# BusPirate-v3_6a-LTS-placed4-plane2-final.net
KiCad netlist of a schematic drawn in EAGLE
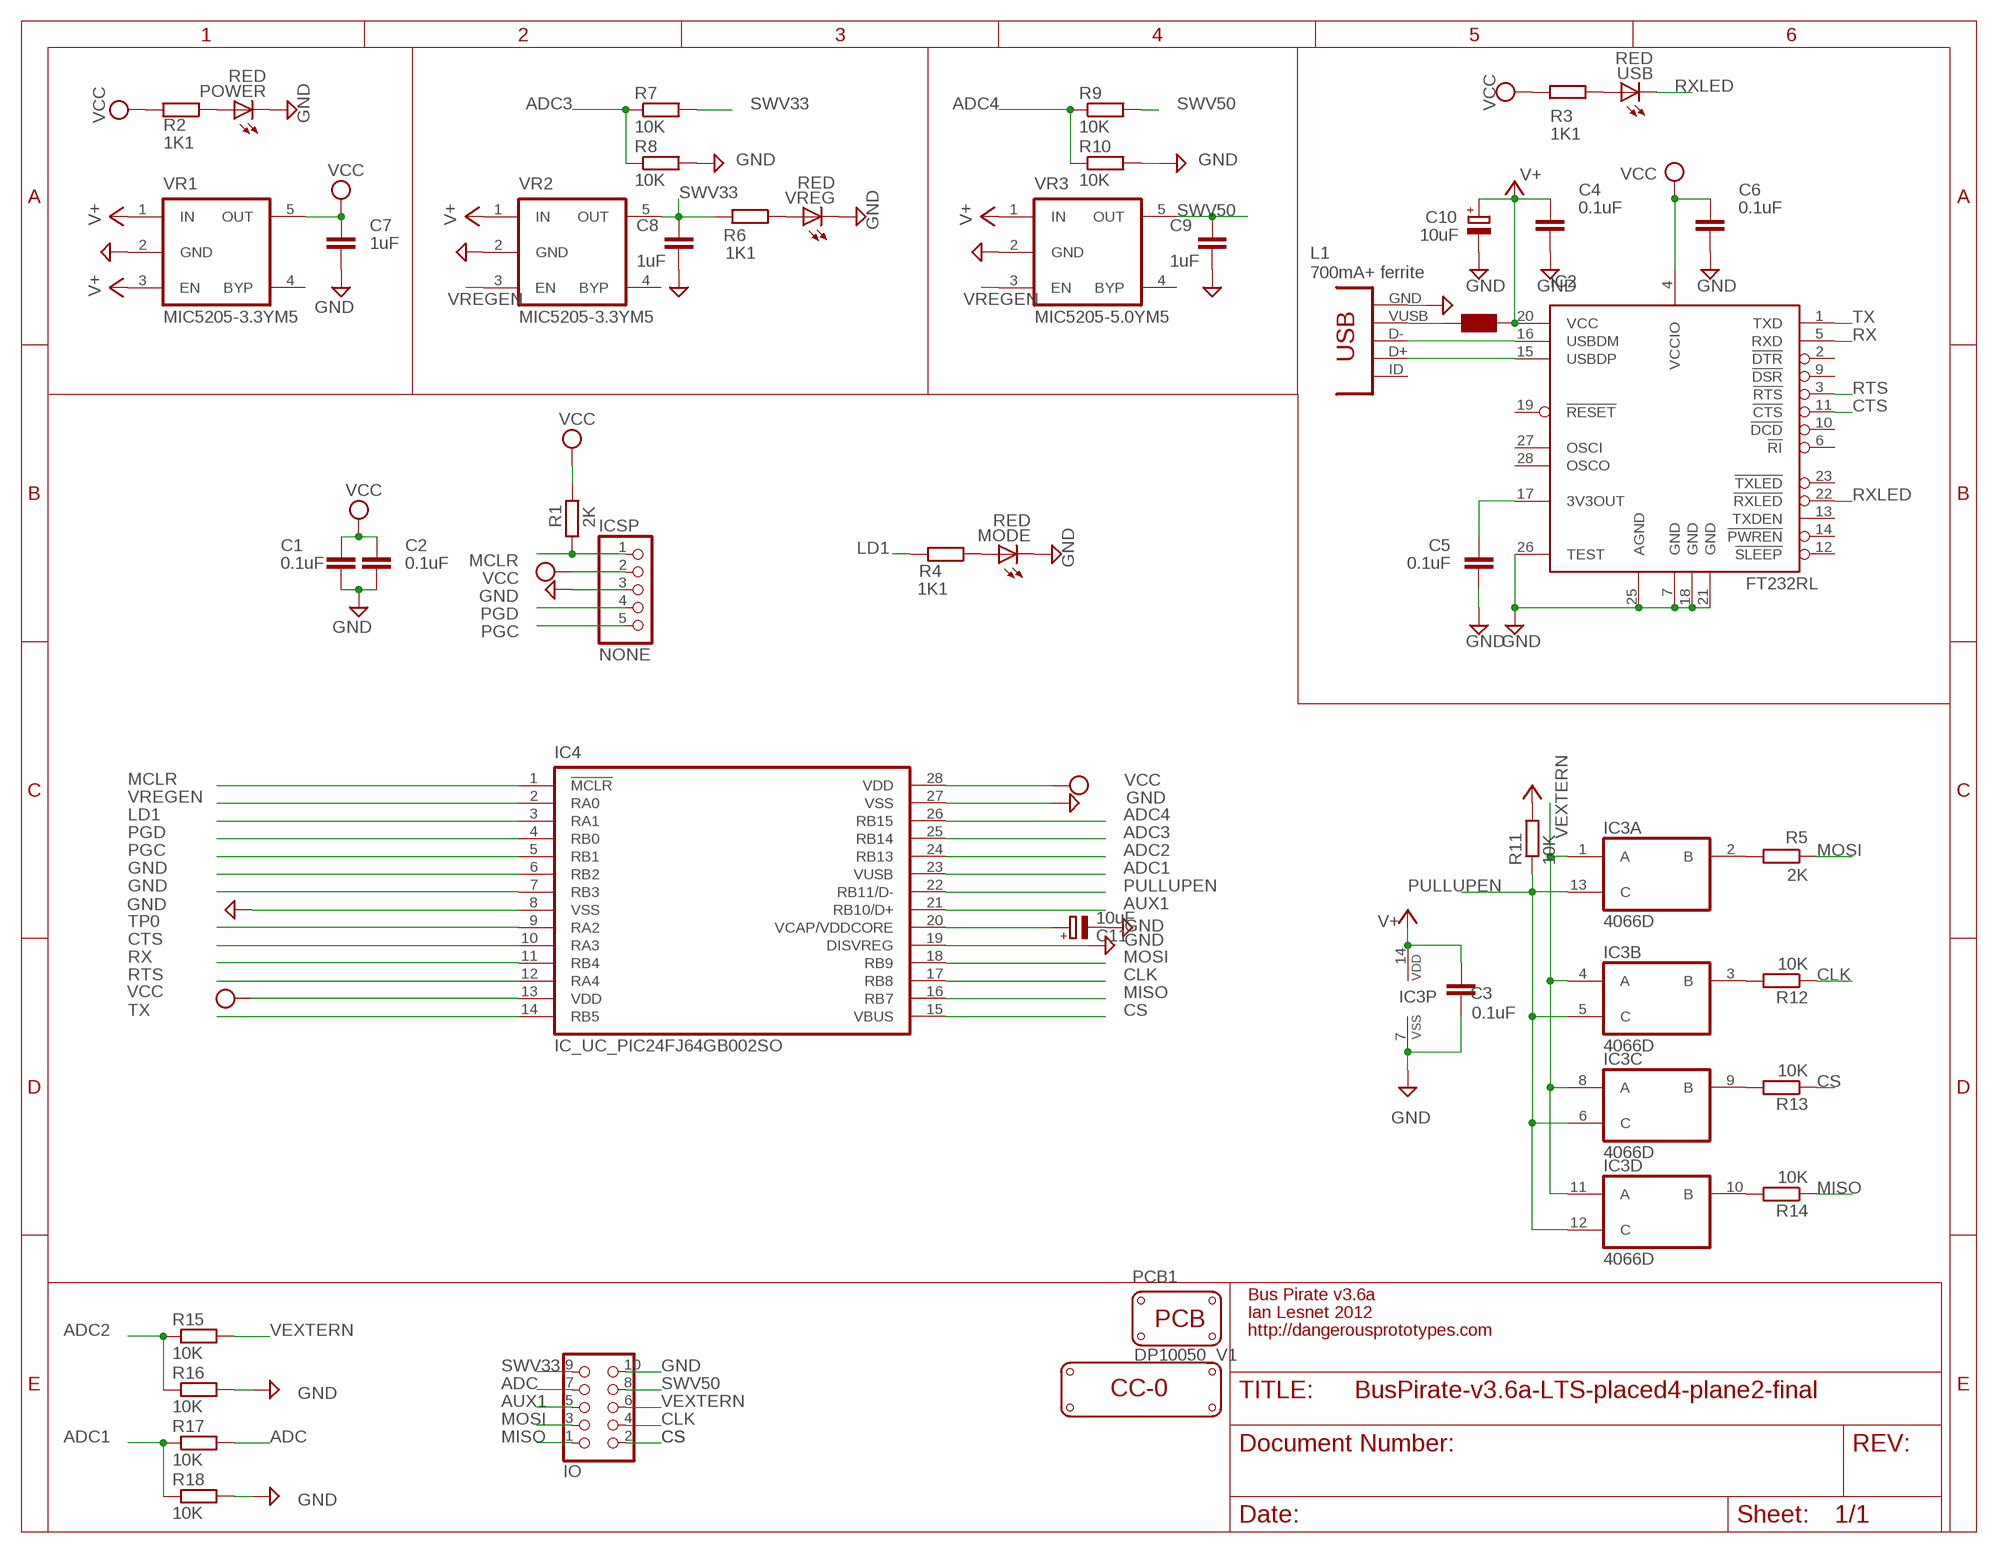
[diagram p0: schematic, sheet 1]

(export (version "E")
  (design (tool "Eeschema 10.0.6"))
  (components
    (comp (ref "C1")
      (value "0.1uF")
      (footprint "eagle-import:C1206")
      (libsource (lib "eagle-import") (part "C-EUC1206"))
    )
    (comp (ref "C2")
      (value "0.1uF")
      (footprint "eagle-import:C1206")
      (libsource (lib "eagle-import") (part "C-EUC1206"))
    )
    (comp (ref "C3")
      (value "0.1uF")
      (footprint "eagle-import:C1206")
      (libsource (lib "eagle-import") (part "C-EUC1206"))
    )
    (comp (ref "C4")
      (value "0.1uF")
      (footprint "eagle-import:C1206")
      (libsource (lib "eagle-import") (part "C-EUC1206"))
    )
    (comp (ref "C5")
      (value "0.1uF")
      (footprint "eagle-import:C1206")
      (libsource (lib "eagle-import") (part "C-EUC1206"))
    )
    (comp (ref "C6")
      (value "0.1uF")
      (footprint "eagle-import:C1206")
      (libsource (lib "eagle-import") (part "C-EUC1206"))
    )
    (comp (ref "C7")
      (value "1uF")
      (footprint "eagle-import:C1206")
      (libsource (lib "eagle-import") (part "C-EUC1206"))
    )
    (comp (ref "C8")
      (value "1uF")
      (footprint "eagle-import:C1206")
      (libsource (lib "eagle-import") (part "C-EUC1206"))
    )
    (comp (ref "C9")
      (value "1uF")
      (footprint "eagle-import:C1206")
      (libsource (lib "eagle-import") (part "C-EUC1206"))
    )
    (comp (ref "C10")
      (value "10uF")
      (footprint "eagle-import:CT3528")
      (libsource (lib "eagle-import") (part "CPOL-EUCT3528"))
    )
    (comp (ref "C11")
      (value "10uF")
      (footprint "eagle-import:CT3528")
      (libsource (lib "eagle-import") (part "CPOL-EUCT3528"))
    )
    (comp (ref "IC2")
      (value "FT232RL")
      (footprint "eagle-import:SSOP28")
      (libsource (lib "eagle-import") (part "FT232RL"))
    )
    (comp (ref "IC3")
      (value "4066D")
      (footprint "eagle-import:SO14")
      (libsource (lib "eagle-import") (part "4066D"))
    )
    (comp (ref "IC4")
      (value "IC_UC_PIC24FJ64GB002SO")
      (footprint "eagle-import:SOIC-28W")
      (libsource (lib "eagle-import") (part "IC_UC_PIC24FJ64GB002SO"))
    )
    (comp (ref "ICSP")
      (value "NONE")
      (footprint "eagle-import:1X05")
      (libsource (lib "eagle-import") (part "PINHD-1X5"))
    )
    (comp (ref "IO")
      (value "CON_HEADER_2X05-PTH+SHROUDED_B")
      (footprint "eagle-import:PINSHRD_PTH_2X05B")
      (libsource (lib "eagle-import") (part "CON_HEADER_2X05-PTH+SHROUDED_B"))
    )
    (comp (ref "J1")
      (value "CON-USB-MINI-BUSB1")
      (footprint "eagle-import:CONN_USB_MINI-B")
      (libsource (lib "eagle-import") (part "CON-USB-MINI-BUSB1"))
    )
    (comp (ref "L1")
      (value "700mA+ ferrite")
      (footprint "eagle-import:WE-KI_0805_B")
      (libsource (lib "eagle-import") (part "WE-KIL_0805"))
    )
    (comp (ref "LOGO1")
      (value "LOGO_CC-0")
      (footprint "eagle-import:LOGO_CC-0")
      (libsource (lib "eagle-import") (part "LOGO_CC-0"))
    )
    (comp (ref "MODE")
      (value "RED")
      (footprint "eagle-import:CHIPLED_1206")
      (libsource (lib "eagle-import") (part "LEDCHIPLED_1206"))
    )
    (comp (ref "PCB1")
      (value "PCB_DP_RECTANGLE-50X100")
      (footprint "eagle-import:DP10050_V1")
      (libsource (lib "eagle-import") (part "PCB_DP_RECTANGLE-50X100"))
    )
    (comp (ref "POWER")
      (value "RED")
      (footprint "eagle-import:CHIPLED_1206")
      (libsource (lib "eagle-import") (part "LEDCHIPLED_1206"))
    )
    (comp (ref "R1")
      (value "2K")
      (footprint "eagle-import:R1206")
      (libsource (lib "eagle-import") (part "R-EU_R1206"))
    )
    (comp (ref "R2")
      (value "1K1")
      (footprint "eagle-import:R1206")
      (libsource (lib "eagle-import") (part "R-EU_R1206"))
    )
    (comp (ref "R3")
      (value "1K1")
      (footprint "eagle-import:R1206")
      (libsource (lib "eagle-import") (part "R-EU_R1206"))
    )
    (comp (ref "R4")
      (value "1K1")
      (footprint "eagle-import:R1206")
      (libsource (lib "eagle-import") (part "R-EU_R1206"))
    )
    (comp (ref "R5")
      (value "2K")
      (footprint "eagle-import:R1206")
      (libsource (lib "eagle-import") (part "R-EU_R1206"))
    )
    (comp (ref "R6")
      (value "1K1")
      (footprint "eagle-import:R1206")
      (libsource (lib "eagle-import") (part "R-EU_R1206"))
    )
    (comp (ref "R7")
      (value "10K")
      (footprint "eagle-import:R1206")
      (libsource (lib "eagle-import") (part "R-EU_R1206"))
    )
    (comp (ref "R8")
      (value "10K")
      (footprint "eagle-import:R1206")
      (libsource (lib "eagle-import") (part "R-EU_R1206"))
    )
    (comp (ref "R9")
      (value "10K")
      (footprint "eagle-import:R1206")
      (libsource (lib "eagle-import") (part "R-EU_R1206"))
    )
    (comp (ref "R10")
      (value "10K")
      (footprint "eagle-import:R1206")
      (libsource (lib "eagle-import") (part "R-EU_R1206"))
    )
    (comp (ref "R11")
      (value "10K")
      (footprint "eagle-import:R1206")
      (libsource (lib "eagle-import") (part "R-EU_R1206"))
    )
    (comp (ref "R12")
      (value "10K")
      (footprint "eagle-import:R1206")
      (libsource (lib "eagle-import") (part "R-EU_R1206"))
    )
    (comp (ref "R13")
      (value "10K")
      (footprint "eagle-import:R1206")
      (libsource (lib "eagle-import") (part "R-EU_R1206"))
    )
    (comp (ref "R14")
      (value "10K")
      (footprint "eagle-import:R1206")
      (libsource (lib "eagle-import") (part "R-EU_R1206"))
    )
    (comp (ref "R15")
      (value "10K")
      (footprint "eagle-import:R1206")
      (libsource (lib "eagle-import") (part "R-EU_R1206"))
    )
    (comp (ref "R16")
      (value "10K")
      (footprint "eagle-import:R1206")
      (libsource (lib "eagle-import") (part "R-EU_R1206"))
    )
    (comp (ref "R17")
      (value "10K")
      (footprint "eagle-import:R1206")
      (libsource (lib "eagle-import") (part "R-EU_R1206"))
    )
    (comp (ref "R18")
      (value "10K")
      (footprint "eagle-import:R1206")
      (libsource (lib "eagle-import") (part "R-EU_R1206"))
    )
    (comp (ref "USB")
      (value "RED")
      (footprint "eagle-import:CHIPLED_1206")
      (libsource (lib "eagle-import") (part "LEDCHIPLED_1206"))
    )
    (comp (ref "VR1")
      (value "MIC5205-3.3YM5")
      (footprint "eagle-import:SOT-23-5")
      (libsource (lib "eagle-import") (part "MIC5205"))
    )
    (comp (ref "VR2")
      (value "MIC5205-3.3YM5")
      (footprint "eagle-import:SOT-23-5")
      (libsource (lib "eagle-import") (part "MIC5205"))
    )
    (comp (ref "VR3")
      (value "MIC5205-5.0YM5")
      (footprint "eagle-import:SOT-23-5")
      (libsource (lib "eagle-import") (part "MIC5205"))
    )
    (comp (ref "VREG")
      (value "RED")
      (footprint "eagle-import:CHIPLED_1206")
      (libsource (lib "eagle-import") (part "LEDCHIPLED_1206"))
    )
  )
  (nets
    (net (code "1") (name "/ADC") (class "Default")
      (node (ref "IO") (pin "7") (pinfunction "7_7") (pintype "passive"))
      (node (ref "R17") (pin "2") (pinfunction "2_2") (pintype "passive"))
    )
    (net (code "2") (name "/ADC1") (class "Default")
      (node (ref "IC4") (pin "23") (pinfunction "VUSB_23") (pintype "bidirectional"))
      (node (ref "R17") (pin "1") (pinfunction "1_1") (pintype "passive"))
      (node (ref "R18") (pin "1") (pinfunction "1_1") (pintype "passive"))
    )
    (net (code "3") (name "/ADC2") (class "Default")
      (node (ref "IC4") (pin "24") (pinfunction "RB13_24") (pintype "bidirectional"))
      (node (ref "R15") (pin "1") (pinfunction "1_1") (pintype "passive"))
      (node (ref "R16") (pin "1") (pinfunction "1_1") (pintype "passive"))
    )
    (net (code "4") (name "/ADC3") (class "Default")
      (node (ref "IC4") (pin "25") (pinfunction "RB14_25") (pintype "bidirectional"))
      (node (ref "R7") (pin "1") (pinfunction "1_1") (pintype "passive"))
      (node (ref "R8") (pin "1") (pinfunction "1_1") (pintype "passive"))
    )
    (net (code "5") (name "/ADC4") (class "Default")
      (node (ref "IC4") (pin "26") (pinfunction "RB15_26") (pintype "bidirectional"))
      (node (ref "R10") (pin "1") (pinfunction "1_1") (pintype "passive"))
      (node (ref "R9") (pin "1") (pinfunction "1_1") (pintype "passive"))
    )
    (net (code "6") (name "/AUX1") (class "Default")
      (node (ref "IC4") (pin "21") (pinfunction "RB10/D+_21") (pintype "bidirectional"))
      (node (ref "IO") (pin "5") (pinfunction "5_5") (pintype "passive"))
    )
    (net (code "7") (name "/CLK") (class "Default")
      (node (ref "IC4") (pin "17") (pinfunction "RB8_17") (pintype "bidirectional"))
      (node (ref "IO") (pin "4") (pinfunction "4_4") (pintype "passive"))
      (node (ref "R12") (pin "1") (pinfunction "1_1") (pintype "passive"))
    )
    (net (code "8") (name "/CS") (class "Default")
      (node (ref "IC4") (pin "15") (pinfunction "VBUS_15") (pintype "power_in"))
      (node (ref "IO") (pin "2") (pinfunction "2_2") (pintype "passive"))
      (node (ref "R13") (pin "1") (pinfunction "1_1") (pintype "passive"))
    )
    (net (code "9") (name "/CTS") (class "Default")
      (node (ref "IC2") (pin "11") (pinfunction "~{CTS}_11") (pintype "bidirectional"))
      (node (ref "IC4") (pin "10") (pinfunction "RA3_10") (pintype "bidirectional"))
    )
    (net (code "10") (name "/LD1") (class "Default")
      (node (ref "IC4") (pin "3") (pinfunction "RA1_3") (pintype "bidirectional"))
      (node (ref "R4") (pin "2") (pinfunction "2_2") (pintype "passive"))
    )
    (net (code "11") (name "/MCLR") (class "Default")
      (node (ref "IC4") (pin "1") (pinfunction "~{MCLR}_1") (pintype "bidirectional"))
      (node (ref "ICSP") (pin "1") (pinfunction "1_1") (pintype "passive"))
      (node (ref "R1") (pin "1") (pinfunction "1_1") (pintype "passive"))
    )
    (net (code "12") (name "/MISO") (class "Default")
      (node (ref "IC4") (pin "16") (pinfunction "RB7_16") (pintype "bidirectional"))
      (node (ref "IO") (pin "1") (pinfunction "1_1") (pintype "passive"))
      (node (ref "R14") (pin "1") (pinfunction "1_1") (pintype "passive"))
    )
    (net (code "13") (name "/MOSI") (class "Default")
      (node (ref "IC4") (pin "18") (pinfunction "RB9_18") (pintype "bidirectional"))
      (node (ref "IO") (pin "3") (pinfunction "3_3") (pintype "passive"))
      (node (ref "R5") (pin "1") (pinfunction "1_1") (pintype "passive"))
    )
    (net (code "14") (name "/PGC") (class "Default")
      (node (ref "IC4") (pin "5") (pinfunction "RB1_5") (pintype "bidirectional"))
      (node (ref "ICSP") (pin "5") (pinfunction "5_5") (pintype "passive"))
    )
    (net (code "15") (name "/PGD") (class "Default")
      (node (ref "IC4") (pin "4") (pinfunction "RB0_4") (pintype "bidirectional"))
      (node (ref "ICSP") (pin "4") (pinfunction "4_4") (pintype "passive"))
    )
    (net (code "16") (name "/PULLUPEN") (class "Default")
      (node (ref "IC3") (pin "12") (pinfunction "C_12") (pintype "input"))
      (node (ref "IC3") (pin "13") (pinfunction "C_13") (pintype "input"))
      (node (ref "IC3") (pin "5") (pinfunction "C_5") (pintype "input"))
      (node (ref "IC3") (pin "6") (pinfunction "C_6") (pintype "input"))
      (node (ref "IC4") (pin "22") (pinfunction "RB11/D-_22") (pintype "bidirectional"))
      (node (ref "R11") (pin "1") (pinfunction "1_1") (pintype "passive"))
    )
    (net (code "17") (name "/RTS") (class "Default")
      (node (ref "IC2") (pin "3") (pinfunction "~{RTS}_3") (pintype "bidirectional"))
      (node (ref "IC4") (pin "12") (pinfunction "RA4_12") (pintype "bidirectional"))
    )
    (net (code "18") (name "/RX") (class "Default")
      (node (ref "IC2") (pin "5") (pinfunction "RXD_5") (pintype "bidirectional"))
      (node (ref "IC4") (pin "11") (pinfunction "RB4_11") (pintype "bidirectional"))
    )
    (net (code "19") (name "/RXLED") (class "Default")
      (node (ref "IC2") (pin "22") (pinfunction "~{RXLED}_22") (pintype "bidirectional"))
      (node (ref "USB") (pin "C") (pinfunction "C_C") (pintype "passive"))
    )
    (net (code "20") (name "/SWV33") (class "Default")
      (node (ref "C8") (pin "1") (pinfunction "1_1") (pintype "passive"))
      (node (ref "IO") (pin "9") (pinfunction "9_9") (pintype "passive"))
      (node (ref "R6") (pin "2") (pinfunction "2_2") (pintype "passive"))
      (node (ref "R7") (pin "2") (pinfunction "2_2") (pintype "passive"))
      (node (ref "VR2") (pin "5") (pinfunction "OUT_5") (pintype "bidirectional"))
    )
    (net (code "21") (name "/SWV50") (class "Default")
      (node (ref "C9") (pin "1") (pinfunction "1_1") (pintype "passive"))
      (node (ref "IO") (pin "8") (pinfunction "8_8") (pintype "passive"))
      (node (ref "R9") (pin "2") (pinfunction "2_2") (pintype "passive"))
      (node (ref "VR3") (pin "5") (pinfunction "OUT_5") (pintype "bidirectional"))
    )
    (net (code "22") (name "/TP0") (class "Default")
      (node (ref "IC4") (pin "9") (pinfunction "RA2_9") (pintype "bidirectional"))
    )
    (net (code "23") (name "/TX") (class "Default")
      (node (ref "IC2") (pin "1") (pinfunction "TXD_1") (pintype "bidirectional"))
      (node (ref "IC4") (pin "14") (pinfunction "RB5_14") (pintype "bidirectional"))
    )
    (net (code "24") (name "/VEXTERN") (class "Default")
      (node (ref "IC3") (pin "1") (pinfunction "A_1") (pintype "tri_state"))
      (node (ref "IC3") (pin "11") (pinfunction "A_11") (pintype "tri_state"))
      (node (ref "IC3") (pin "4") (pinfunction "A_4") (pintype "tri_state"))
      (node (ref "IC3") (pin "8") (pinfunction "A_8") (pintype "tri_state"))
      (node (ref "IO") (pin "6") (pinfunction "6_6") (pintype "passive"))
      (node (ref "R15") (pin "2") (pinfunction "2_2") (pintype "passive"))
    )
    (net (code "25") (name "/VREGEN") (class "Default")
      (node (ref "IC4") (pin "2") (pinfunction "RA0_2") (pintype "bidirectional"))
      (node (ref "VR2") (pin "3") (pinfunction "EN_3") (pintype "bidirectional"))
      (node (ref "VR3") (pin "3") (pinfunction "EN_3") (pintype "bidirectional"))
    )
    (net (code "26") (name "GND") (class "Default")
      (node (ref "C1") (pin "2") (pinfunction "2_2") (pintype "passive"))
      (node (ref "C10") (pin "-") (pinfunction "-_-") (pintype "passive"))
      (node (ref "C11") (pin "-") (pinfunction "-_-") (pintype "passive"))
      (node (ref "C2") (pin "2") (pinfunction "2_2") (pintype "passive"))
      (node (ref "C3") (pin "2") (pinfunction "2_2") (pintype "passive"))
      (node (ref "C4") (pin "2") (pinfunction "2_2") (pintype "passive"))
      (node (ref "C5") (pin "2") (pinfunction "2_2") (pintype "passive"))
      (node (ref "C6") (pin "2") (pinfunction "2_2") (pintype "passive"))
      (node (ref "C7") (pin "2") (pinfunction "2_2") (pintype "passive"))
      (node (ref "C8") (pin "2") (pinfunction "2_2") (pintype "passive"))
      (node (ref "C9") (pin "2") (pinfunction "2_2") (pintype "passive"))
      (node (ref "IC2") (pin "18") (pinfunction "GND_18") (pintype "bidirectional"))
      (node (ref "IC2") (pin "21") (pinfunction "GND_21") (pintype "bidirectional"))
      (node (ref "IC2") (pin "25") (pinfunction "AGND_25") (pintype "bidirectional"))
      (node (ref "IC2") (pin "26") (pinfunction "TEST_26") (pintype "bidirectional"))
      (node (ref "IC2") (pin "7") (pinfunction "GND_7") (pintype "bidirectional"))
      (node (ref "IC3") (pin "7") (pinfunction "VSS_7") (pintype "power_in"))
      (node (ref "IC4") (pin "19") (pinfunction "DISVREG_19") (pintype "passive"))
      (node (ref "IC4") (pin "27") (pinfunction "VSS_27") (pintype "power_in"))
      (node (ref "IC4") (pin "6") (pinfunction "RB2_6") (pintype "bidirectional"))
      (node (ref "IC4") (pin "7") (pinfunction "RB3_7") (pintype "bidirectional"))
      (node (ref "IC4") (pin "8") (pinfunction "VSS_8") (pintype "power_in"))
      (node (ref "ICSP") (pin "3") (pinfunction "3_3") (pintype "passive"))
      (node (ref "IO") (pin "10") (pinfunction "10_10") (pintype "passive"))
      (node (ref "J1") (pin "GND") (pinfunction "GND_GND") (pintype "bidirectional"))
      (node (ref "MODE") (pin "C") (pinfunction "C_C") (pintype "passive"))
      (node (ref "POWER") (pin "C") (pinfunction "C_C") (pintype "passive"))
      (node (ref "R10") (pin "2") (pinfunction "2_2") (pintype "passive"))
      (node (ref "R16") (pin "2") (pinfunction "2_2") (pintype "passive"))
      (node (ref "R18") (pin "2") (pinfunction "2_2") (pintype "passive"))
      (node (ref "R8") (pin "2") (pinfunction "2_2") (pintype "passive"))
      (node (ref "VR1") (pin "2") (pinfunction "GND_2") (pintype "bidirectional"))
      (node (ref "VR2") (pin "2") (pinfunction "GND_2") (pintype "bidirectional"))
      (node (ref "VR3") (pin "2") (pinfunction "GND_2") (pintype "bidirectional"))
      (node (ref "VREG") (pin "C") (pinfunction "C_C") (pintype "passive"))
    )
    (net (code "27") (name "Net-(IC2-3V3OUT)") (class "Default")
      (node (ref "C5") (pin "1") (pinfunction "1_1") (pintype "passive"))
      (node (ref "IC2") (pin "17") (pinfunction "3V3OUT_17") (pintype "bidirectional"))
    )
    (net (code "28") (name "Net-(IC2-USBDM)") (class "Default")
      (node (ref "IC2") (pin "16") (pinfunction "USBDM_16") (pintype "bidirectional"))
      (node (ref "J1") (pin "D-") (pinfunction "D-_D-") (pintype "bidirectional"))
    )
    (net (code "29") (name "Net-(IC2-USBDP)") (class "Default")
      (node (ref "IC2") (pin "15") (pinfunction "USBDP_15") (pintype "bidirectional"))
      (node (ref "J1") (pin "D+") (pinfunction "D+_D+") (pintype "bidirectional"))
    )
    (net (code "30") (name "Net-(IC3A-B)") (class "Default")
      (node (ref "IC3") (pin "2") (pinfunction "B_2") (pintype "tri_state"))
      (node (ref "R5") (pin "2") (pinfunction "2_2") (pintype "passive"))
    )
    (net (code "31") (name "Net-(IC3B-B)") (class "Default")
      (node (ref "IC3") (pin "3") (pinfunction "B_3") (pintype "tri_state"))
      (node (ref "R12") (pin "2") (pinfunction "2_2") (pintype "passive"))
    )
    (net (code "32") (name "Net-(IC3C-B)") (class "Default")
      (node (ref "IC3") (pin "9") (pinfunction "B_9") (pintype "tri_state"))
      (node (ref "R13") (pin "2") (pinfunction "2_2") (pintype "passive"))
    )
    (net (code "33") (name "Net-(IC3D-B)") (class "Default")
      (node (ref "IC3") (pin "10") (pinfunction "B_10") (pintype "tri_state"))
      (node (ref "R14") (pin "2") (pinfunction "2_2") (pintype "passive"))
    )
    (net (code "34") (name "Net-(IC4-VCAP{slash}VDDCORE)") (class "Default")
      (node (ref "C11") (pin "+") (pinfunction "+_+") (pintype "passive"))
      (node (ref "IC4") (pin "20") (pinfunction "VCAP/VDDCORE_20") (pintype "power_in"))
    )
    (net (code "35") (name "Net-(L1-1)") (class "Default")
      (node (ref "J1") (pin "VUSB") (pinfunction "VUSB_VUSB") (pintype "bidirectional"))
      (node (ref "L1") (pin "2") (pinfunction "1_2") (pintype "passive"))
    )
    (net (code "36") (name "Net-(MODE-PadA)") (class "Default")
      (node (ref "MODE") (pin "A") (pinfunction "A_A") (pintype "passive"))
      (node (ref "R4") (pin "1") (pinfunction "1_1") (pintype "passive"))
    )
    (net (code "37") (name "Net-(POWER-PadA)") (class "Default")
      (node (ref "POWER") (pin "A") (pinfunction "A_A") (pintype "passive"))
      (node (ref "R2") (pin "1") (pinfunction "1_1") (pintype "passive"))
    )
    (net (code "38") (name "Net-(R3-Pad1)") (class "Default")
      (node (ref "R3") (pin "1") (pinfunction "1_1") (pintype "passive"))
      (node (ref "USB") (pin "A") (pinfunction "A_A") (pintype "passive"))
    )
    (net (code "39") (name "Net-(R6-Pad1)") (class "Default")
      (node (ref "R6") (pin "1") (pinfunction "1_1") (pintype "passive"))
      (node (ref "VREG") (pin "A") (pinfunction "A_A") (pintype "passive"))
    )
    (net (code "40") (name "V+") (class "Default")
      (node (ref "C10") (pin "+") (pinfunction "+_+") (pintype "passive"))
      (node (ref "C3") (pin "1") (pinfunction "1_1") (pintype "passive"))
      (node (ref "C4") (pin "1") (pinfunction "1_1") (pintype "passive"))
      (node (ref "IC2") (pin "20") (pinfunction "VCC_20") (pintype "bidirectional"))
      (node (ref "IC3") (pin "14") (pinfunction "VDD_14") (pintype "power_in"))
      (node (ref "L1") (pin "1") (pinfunction "2_1") (pintype "passive"))
      (node (ref "R11") (pin "2") (pinfunction "2_2") (pintype "passive"))
      (node (ref "VR1") (pin "1") (pinfunction "IN_1") (pintype "bidirectional"))
      (node (ref "VR1") (pin "3") (pinfunction "EN_3") (pintype "bidirectional"))
      (node (ref "VR2") (pin "1") (pinfunction "IN_1") (pintype "bidirectional"))
      (node (ref "VR3") (pin "1") (pinfunction "IN_1") (pintype "bidirectional"))
    )
    (net (code "41") (name "VCC") (class "Default")
      (node (ref "C1") (pin "1") (pinfunction "1_1") (pintype "passive"))
      (node (ref "C2") (pin "1") (pinfunction "1_1") (pintype "passive"))
      (node (ref "C6") (pin "1") (pinfunction "1_1") (pintype "passive"))
      (node (ref "C7") (pin "1") (pinfunction "1_1") (pintype "passive"))
      (node (ref "IC2") (pin "4") (pinfunction "VCCIO_4") (pintype "bidirectional"))
      (node (ref "IC4") (pin "13") (pinfunction "VDD_13") (pintype "power_in"))
      (node (ref "IC4") (pin "28") (pinfunction "VDD_28") (pintype "power_in"))
      (node (ref "ICSP") (pin "2") (pinfunction "2_2") (pintype "passive"))
      (node (ref "R1") (pin "2") (pinfunction "2_2") (pintype "passive"))
      (node (ref "R2") (pin "2") (pinfunction "2_2") (pintype "passive"))
      (node (ref "R3") (pin "2") (pinfunction "2_2") (pintype "passive"))
      (node (ref "VR1") (pin "5") (pinfunction "OUT_5") (pintype "bidirectional"))
    )
    (net (code "42") (name "unconnected-(IC2-OSCI-Pad27)") (class "Default")
      (node (ref "IC2") (pin "27") (pinfunction "OSCI_27") (pintype "bidirectional"))
    )
    (net (code "43") (name "unconnected-(IC2-OSCO-Pad28)") (class "Default")
      (node (ref "IC2") (pin "28") (pinfunction "OSCO_28") (pintype "bidirectional"))
    )
    (net (code "44") (name "unconnected-(IC2-TXDEN-Pad13)") (class "Default")
      (node (ref "IC2") (pin "13") (pinfunction "TXDEN_13") (pintype "bidirectional"))
    )
    (net (code "45") (name "unconnected-(IC2-~{DCD}-Pad10)") (class "Default")
      (node (ref "IC2") (pin "10") (pinfunction "~{DCD}_10") (pintype "bidirectional"))
    )
    (net (code "46") (name "unconnected-(IC2-~{DSR}-Pad9)") (class "Default")
      (node (ref "IC2") (pin "9") (pinfunction "~{DSR}_9") (pintype "bidirectional"))
    )
    (net (code "47") (name "unconnected-(IC2-~{DTR}-Pad2)") (class "Default")
      (node (ref "IC2") (pin "2") (pinfunction "~{DTR}_2") (pintype "bidirectional"))
    )
    (net (code "48") (name "unconnected-(IC2-~{PWREN}-Pad14)") (class "Default")
      (node (ref "IC2") (pin "14") (pinfunction "~{PWREN}_14") (pintype "bidirectional"))
    )
    (net (code "49") (name "unconnected-(IC2-~{RESET}-Pad19)") (class "Default")
      (node (ref "IC2") (pin "19") (pinfunction "~{RESET}_19") (pintype "bidirectional"))
    )
    (net (code "50") (name "unconnected-(IC2-~{RI}-Pad6)") (class "Default")
      (node (ref "IC2") (pin "6") (pinfunction "~{RI}_6") (pintype "bidirectional"))
    )
    (net (code "51") (name "unconnected-(IC2-~{SLEEP}-Pad12)") (class "Default")
      (node (ref "IC2") (pin "12") (pinfunction "~{SLEEP}_12") (pintype "bidirectional"))
    )
    (net (code "52") (name "unconnected-(IC2-~{TXLED}-Pad23)") (class "Default")
      (node (ref "IC2") (pin "23") (pinfunction "~{TXLED}_23") (pintype "bidirectional"))
    )
    (net (code "53") (name "unconnected-(J1B-USBID-PadID)") (class "Default")
      (node (ref "J1") (pin "ID") (pinfunction "USBID_ID") (pintype "bidirectional"))
    )
    (net (code "54") (name "unconnected-(VR1-BYP-Pad4)") (class "Default")
      (node (ref "VR1") (pin "4") (pinfunction "BYP_4") (pintype "bidirectional"))
    )
    (net (code "55") (name "unconnected-(VR2-BYP-Pad4)") (class "Default")
      (node (ref "VR2") (pin "4") (pinfunction "BYP_4") (pintype "bidirectional"))
    )
    (net (code "56") (name "unconnected-(VR3-BYP-Pad4)") (class "Default")
      (node (ref "VR3") (pin "4") (pinfunction "BYP_4") (pintype "bidirectional"))
    )
  )
)
